# TOP_LEVEL.net
KiCad netlist of a schematic drawn in Altium Designer
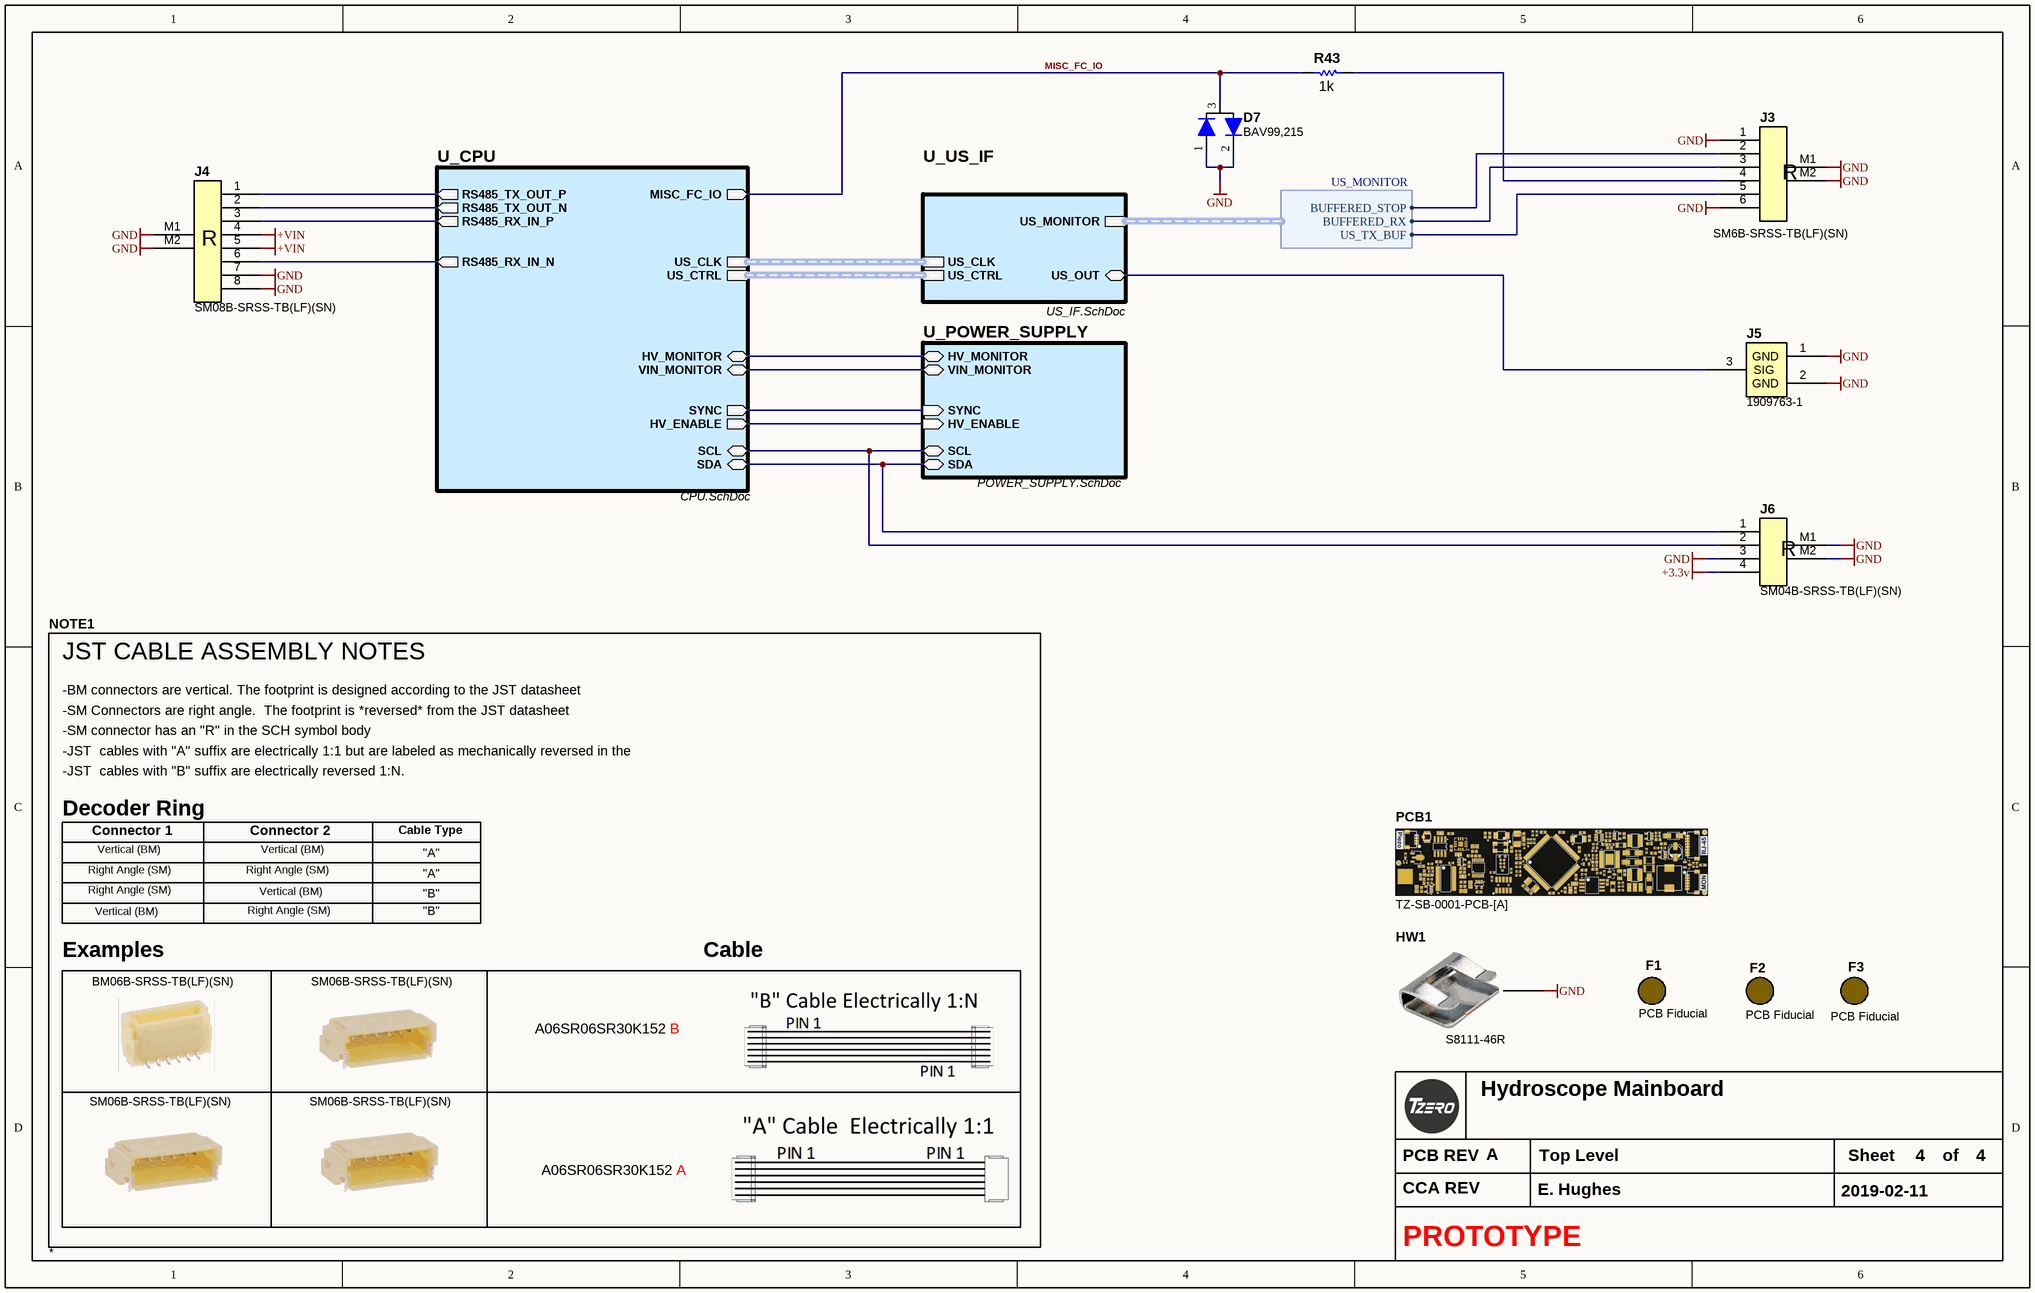
[diagram p0: TOP_LEVEL.SchDoc]

(export (version "E")
  (design (tool "Eeschema 10.0.6"))
  (components
    (comp (ref "D7")
      (value "BAV99,215")
      (footprint "SOT-23")
      (description "DIODE ARRAY GP 100V 215MA SOT23")
      (fields (field (name "MANUFACTURER") "NXP Semiconductors") (field (name "VOLTAGE") "100V"))
      (libsource (lib "eDiode") (part "BAV99,215"))
    )
    (comp (ref "F1")
      (value "PCB Fiducial")
      (footprint "Fiducial 1mm - 2mm")
      (libsource (lib "eFiducial") (part "Fiducial"))
    )
    (comp (ref "F2")
      (value "PCB Fiducial")
      (footprint "Fiducial 1mm - 2mm")
      (libsource (lib "eFiducial") (part "Fiducial"))
    )
    (comp (ref "F3")
      (value "PCB Fiducial")
      (footprint "Fiducial 1mm - 2mm")
      (libsource (lib "eFiducial") (part "Fiducial"))
    )
    (comp (ref "HW1")
      (value "S8111-46R")
      (footprint "S8111-46R")
      (description "CBL CLIP 1-1.5MM DIA CBL SMD")
      (fields (field (name "MANUFACTURER") "Harwin"))
      (libsource (lib "EMechanical") (part "S8111-46R"))
    )
    (comp (ref "J3")
      (value "SM6B-SRSS-TB(LF)(SN)")
      (footprint "SM06B-SRSS-TB(LF)(SN)")
      (description "6 Positions Header, Shrouded Connector 0.039\" (1.00mm) Surface Mount, Right Angle Tin")
      (fields
        (field (name "MANUFACTURER") "JST")
        (field (name "MANUFACTURER PART NUMBER") "SM06B-SRSS-TB(LF)(SN)")
      )
      (libsource (lib "eConnector_JST_SM") (part "SM06B-SRSS-TB(LF)(SN)"))
    )
    (comp (ref "J4")
      (value "SM08B-SRSS-TB(LF)(SN)")
      (footprint "SM08B-SRSS-TB(LF)(SN)")
      (description "8 Positions Header, Shrouded Connector 0.039\" (1.00mm) Surface Mount, Right Angle Tin")
      (fields (field (name "MANUFACTURER") "JST"))
      (libsource (lib "eConnector_JST_SM") (part "SM08B-SRSS-TB(LF)(SN)"))
    )
    (comp (ref "J5")
      (value "1909763-1")
      (footprint "1909763-1")
      (description "CONN UMCC JACK STR 50OHM SMD")
      (fields (field (name "MANUFACTURER") "TE Connectivity AMP Connectors"))
      (libsource (lib "eConnector_RF") (part "1909763-1"))
    )
    (comp (ref "J6")
      (value "SM04B-SRSS-TB(LF)(SN)")
      (footprint "SM04B-SRSS-TB(LF)(SN)")
      (description "Conn Shrouded Header HDR 4 POS 1mm Solder RA SMD T/R")
      (fields (field (name "MANUFACTURER") "JST"))
      (libsource (lib "eConnector_JST_SM") (part "SM04B-SRSS-TB(LF)(SN)"))
    )
    (comp (ref "NOTE1") (value "*") (libsource (lib "Hydroscope") (part "JST_SH_CABLE_ASSEMBLY_NOTES")))
    (comp (ref "PCB1")
      (value "TZ-SB-0001-PCB-[A]")
      (description "Raw printed circuit board,  Revision A")
      (fields (field (name "MANUFACTURER") "TZero"))
      (libsource (lib "ePCB") (part "TZ-SB-0001-PCB-[A]"))
    )
    (comp (ref "R43")
      (value "1k")
      (footprint "R0603_0.55MM_HD")
      (description "RES 1K OHM 1/10W 1% 0603 SMD")
      (fields
        (field (name "MANUFACTURER PART NUMBER") "ERJ-3EKF1001V")
        (field (name "MANUFACTURER") "Panasonic Electronic Components")
      )
      (libsource (lib "Resistors - Panasonic - AEC-Q200") (part "R_2P"))
    )
  )
  (nets
    (net (code "2") (name "+3.3v") (class "Default")
      (node (ref "J6") (pin "4") (pinfunction "4_4") (pintype "passive"))
    )
    (net (code "3") (name "+VIN") (class "Default")
      (node (ref "J4") (pin "4") (pinfunction "4_4") (pintype "passive"))
      (node (ref "J4") (pin "5") (pinfunction "5_5") (pintype "passive"))
    )
    (net (code "4") (name "/BUFFERED_RX") (class "Default")
      (node (ref "J3") (pin "3") (pinfunction "3_3") (pintype "passive"))
    )
    (net (code "5") (name "/BUFFERED_STOP") (class "Default")
      (node (ref "J3") (pin "2") (pinfunction "2_2") (pintype "passive"))
    )
    (net (code "8") (name "/MISC_FC_IO") (class "Default")
      (node (ref "D7") (pin "3") (pinfunction "AC_3") (pintype "passive"))
      (node (ref "R43") (pin "2") (pinfunction "2_2") (pintype "passive"))
    )
    (net (code "9") (name "/RS485_RX_IN_N") (class "Default")
      (node (ref "J4") (pin "6") (pinfunction "6_6") (pintype "passive"))
    )
    (net (code "10") (name "/RS485_RX_IN_P") (class "Default")
      (node (ref "J4") (pin "3") (pinfunction "3_3") (pintype "passive"))
    )
    (net (code "11") (name "/RS485_TX_OUT_N") (class "Default")
      (node (ref "J4") (pin "2") (pinfunction "2_2") (pintype "passive"))
    )
    (net (code "12") (name "/RS485_TX_OUT_P") (class "Default")
      (node (ref "J4") (pin "1") (pinfunction "1_1") (pintype "passive"))
    )
    (net (code "13") (name "/SCL") (class "Default")
      (node (ref "J6") (pin "2") (pinfunction "2_2") (pintype "passive"))
    )
    (net (code "14") (name "/SDA") (class "Default")
      (node (ref "J6") (pin "1") (pinfunction "1_1") (pintype "passive"))
    )
    (net (code "18") (name "/US_OUT") (class "Default")
      (node (ref "J5") (pin "3") (pinfunction "SIG_3") (pintype "passive"))
    )
    (net (code "19") (name "/US_TX_BUF") (class "Default")
      (node (ref "J3") (pin "5") (pinfunction "5_5") (pintype "passive"))
    )
    (net (code "22") (name "GND") (class "Default")
      (node (ref "D7") (pin "1") (pinfunction "A_1") (pintype "passive"))
      (node (ref "D7") (pin "2") (pinfunction "C_2") (pintype "passive"))
      (node (ref "HW1") (pin "1") (pinfunction "1_1") (pintype "passive"))
      (node (ref "J3") (pin "1") (pinfunction "1_1") (pintype "passive"))
      (node (ref "J3") (pin "6") (pinfunction "6_6") (pintype "passive"))
      (node (ref "J3") (pin "M1") (pinfunction "M1_M1") (pintype "passive"))
      (node (ref "J3") (pin "M2") (pinfunction "M2_M2") (pintype "passive"))
      (node (ref "J4") (pin "7") (pinfunction "7_7") (pintype "passive"))
      (node (ref "J4") (pin "8") (pinfunction "8_8") (pintype "passive"))
      (node (ref "J4") (pin "M1") (pinfunction "M1_M1") (pintype "passive"))
      (node (ref "J4") (pin "M2") (pinfunction "M2_M2") (pintype "passive"))
      (node (ref "J5") (pin "1") (pinfunction "GND_1") (pintype "passive"))
      (node (ref "J5") (pin "2") (pinfunction "GND_2") (pintype "passive"))
      (node (ref "J6") (pin "3") (pinfunction "3_3") (pintype "passive"))
      (node (ref "J6") (pin "M1") (pinfunction "M1_M1") (pintype "passive"))
      (node (ref "J6") (pin "M2") (pinfunction "M2_M2") (pintype "passive"))
    )
    (net (code "23") (name "Net-(J3-Pad4)") (class "Default")
      (node (ref "J3") (pin "4") (pinfunction "4_4") (pintype "passive"))
      (node (ref "R43") (pin "1") (pinfunction "1_1") (pintype "passive"))
    )
  )
)
